# SensorSheet.net
KiCad netlist of a schematic drawn in Altium Designer
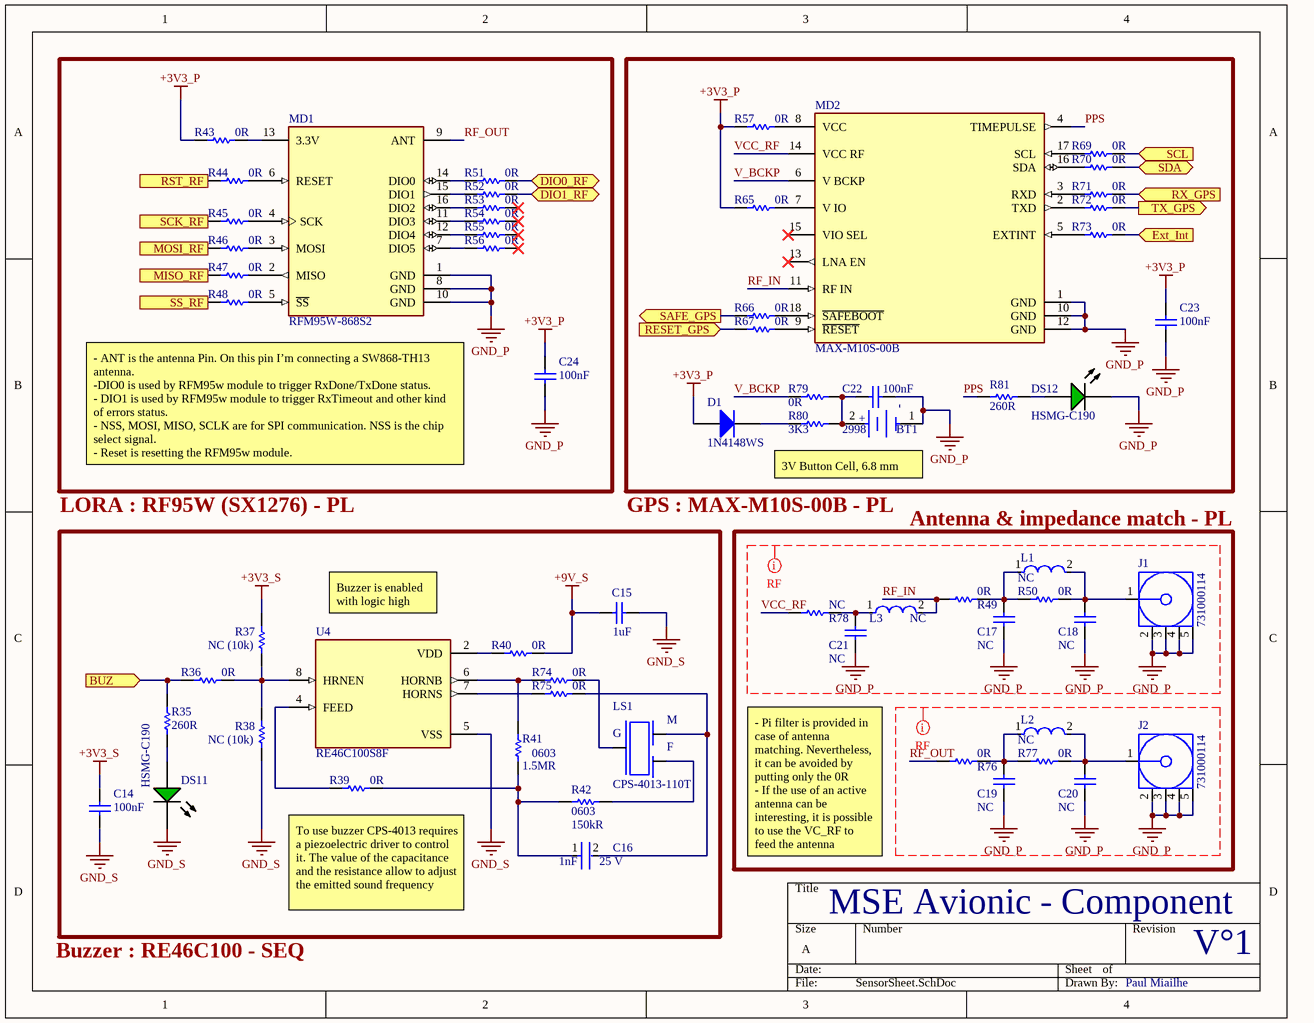
[diagram p0: SensorSheet.SchDoc]

(export (version "E")
  (design (tool "Eeschema 10.0.6"))
  (components
    (comp (ref "BT1")
      (value "2998")
      (footprint "FP-2998-MFG")
      (description "BATTERY RETAINER COIN 6.8MM SMD")
      (libsource (lib "Altium Content Vault") (part "60d3b5b901a8747834971d0eb8cf3fd"))
    )
    (comp (ref "C14")
      (value "GRM21BR71H104KA01L")
      (footprint "CAPC2013X135X45ML10T25")
      (description "Chip Capacitor, 0.1 uF, +/- 10%, 50 V, -55 to 125 degC, 0805 (2012 Metric), RoHS, Tape and Reel")
      (fields
        (field (name "VOLTAGE") "50V")
        (field (name "CAPACITANCE") "100nF")
        (field (name "TOLERANCE") "10%")
      )
      (libsource (lib "Altium Content Vault") (part "CAP-NP-2"))
    )
    (comp (ref "C15")
      (value "GRM188R61E105KA12D")
      (footprint "CAPC1608X90X35LL10T15")
      (fields
        (field (name "MANUFACTURER") "Murata")
        (field (name "CAPACITANCE") "1uF")
        (field (name "TOLERANCE") "10%")
        (field (name "VOLTAGE") "25V")
      )
      (libsource (lib "Altium Content Vault") (part "CAP"))
    )
    (comp (ref "C16")
      (value "C0603C102J3GACTU")
      (footprint "FP-C0603C-CF-MFG")
      (description "CAP CER 1000PF 25V 5% NP0 0603")
      (fields
        (field (name "OCTOPART") "https://octopart.com/c0603c102j3gactu-kemet-8375722")
        (field (name "CAPACITANCE") "1nF")
        (field (name "TOLERANCE") "0.05")
        (field (name "VOLTAGE RATING") "25 V")
      )
      (libsource (lib "Altium Content Vault") (part "b4654b650e69147ec39a6b967a45e02"))
    )
    (comp (ref "C17")
      (value "GRM21BR71H104KA01L")
      (footprint "CAPC2013X135X45ML10T25")
      (description "Chip Capacitor, 0.1 uF, +/- 10%, 50 V, -55 to 125 degC, 0805 (2012 Metric), RoHS, Tape and Reel")
      (fields
        (field (name "VOLTAGE") "50V")
        (field (name "CAPACITANCE") "NC")
        (field (name "TOLERANCE") "10%")
      )
      (libsource (lib "Altium Content Vault") (part "CAP-NP-2"))
    )
    (comp (ref "C18")
      (value "GRM21BR71H104KA01L")
      (footprint "CAPC2013X135X45ML10T25")
      (description "Chip Capacitor, 0.1 uF, +/- 10%, 50 V, -55 to 125 degC, 0805 (2012 Metric), RoHS, Tape and Reel")
      (fields
        (field (name "VOLTAGE") "50V")
        (field (name "CAPACITANCE") "NC")
        (field (name "TOLERANCE") "10%")
      )
      (libsource (lib "Altium Content Vault") (part "CAP-NP-2"))
    )
    (comp (ref "C19")
      (value "GRM21BR71H104KA01L")
      (footprint "CAPC2013X135X45ML10T25")
      (description "Chip Capacitor, 0.1 uF, +/- 10%, 50 V, -55 to 125 degC, 0805 (2012 Metric), RoHS, Tape and Reel")
      (fields
        (field (name "VOLTAGE") "50V")
        (field (name "CAPACITANCE") "NC")
        (field (name "TOLERANCE") "10%")
      )
      (libsource (lib "Altium Content Vault") (part "CAP-NP-2"))
    )
    (comp (ref "C20")
      (value "GRM21BR71H104KA01L")
      (footprint "CAPC2013X135X45ML10T25")
      (description "Chip Capacitor, 0.1 uF, +/- 10%, 50 V, -55 to 125 degC, 0805 (2012 Metric), RoHS, Tape and Reel")
      (fields
        (field (name "VOLTAGE") "50V")
        (field (name "CAPACITANCE") "NC")
        (field (name "TOLERANCE") "10%")
      )
      (libsource (lib "Altium Content Vault") (part "CAP-NP-2"))
    )
    (comp (ref "C21")
      (value "GRM21BR71H104KA01L")
      (footprint "CAPC2013X135X45ML10T25")
      (description "Chip Capacitor, 0.1 uF, +/- 10%, 50 V, -55 to 125 degC, 0805 (2012 Metric), RoHS, Tape and Reel")
      (fields
        (field (name "VOLTAGE") "50V")
        (field (name "CAPACITANCE") "NC")
        (field (name "TOLERANCE") "10%")
      )
      (libsource (lib "Altium Content Vault") (part "CAP-NP-2"))
    )
    (comp (ref "C22")
      (value "GRM21BR71H104KA01L")
      (footprint "CAPC2013X135X45ML10T25")
      (description "Chip Capacitor, 0.1 uF, +/- 10%, 50 V, -55 to 125 degC, 0805 (2012 Metric), RoHS, Tape and Reel")
      (fields
        (field (name "VOLTAGE") "50V")
        (field (name "CAPACITANCE") "100nF")
        (field (name "TOLERANCE") "10%")
      )
      (libsource (lib "Altium Content Vault") (part "CAP-NP-2"))
    )
    (comp (ref "C23")
      (value "GRM21BR71H104KA01L")
      (footprint "CAPC2013X135X45ML10T25")
      (description "Chip Capacitor, 0.1 uF, +/- 10%, 50 V, -55 to 125 degC, 0805 (2012 Metric), RoHS, Tape and Reel")
      (fields
        (field (name "VOLTAGE") "50V")
        (field (name "CAPACITANCE") "100nF")
        (field (name "TOLERANCE") "10%")
      )
      (libsource (lib "Altium Content Vault") (part "CAP-NP-2"))
    )
    (comp (ref "C24")
      (value "GRM21BR71H104KA01L")
      (footprint "CAPC2013X135X45ML10T25")
      (description "Chip Capacitor, 0.1 uF, +/- 10%, 50 V, -55 to 125 degC, 0805 (2012 Metric), RoHS, Tape and Reel")
      (fields
        (field (name "VOLTAGE") "50V")
        (field (name "CAPACITANCE") "100nF")
        (field (name "TOLERANCE") "10%")
      )
      (libsource (lib "Altium Content Vault") (part "CAP-NP-2"))
    )
    (comp (ref "D1")
      (value "1N4148WS")
      (footprint "FAIR-SOD-323_V")
      (description "Small Signal Diode, 75 V, 0.15 A, -55 to 150 degC, 2-Pin SOD-323, RoHS, Tape and Reel")
      (fields (field (name "MANUFACTURER") "Fairchild"))
      (libsource (lib "Saint-Étienne School of Mines- Mines Space") (part "D-AK-2"))
    )
    (comp (ref "DS11")
      (value "HSMG-C190")
      (footprint "AVAG-HSMX-C190_V")
      (description "Chip LED, Green, 2.2 V, -40 to 85 degC, 2-Pin SMD, RoHS, Tape and Reel")
      (libsource (lib "Altium Content Vault") (part "LED-GREEN-AK-2"))
    )
    (comp (ref "DS12")
      (value "HSMG-C190")
      (footprint "AVAG-HSMX-C190_V")
      (description "Chip LED, Green, 2.2 V, -40 to 85 degC, 2-Pin SMD, RoHS, Tape and Reel")
      (libsource (lib "Altium Content Vault") (part "LED-GREEN-AK-2"))
    )
    (comp (ref "J1")
      (value "731000114")
      (footprint "MOLX-731000114_V")
      (description "SMA Right-Angle PCB Jack Receptacle, Brass Body, Gold Plated, 50 Ohm, 5-Pin THD, RoHS, Tray")
      (fields (field (name "MANUFACTURER") "Molex"))
      (libsource (lib "Altium Content Vault") (part "CN-S-4F-RF5"))
    )
    (comp (ref "J2")
      (value "731000114")
      (footprint "MOLX-731000114_V")
      (description "SMA Right-Angle PCB Jack Receptacle, Brass Body, Gold Plated, 50 Ohm, 5-Pin THD, RoHS, Tray")
      (fields (field (name "MANUFACTURER") "Molex"))
      (libsource (lib "Altium Content Vault") (part "CN-S-4F-RF5"))
    )
    (comp (ref "L1")
      (value "NC")
      (footprint "FP-B82422A-MFG")
      (description "FIXED IND 10UH 180MA 1.6 OHM SMD")
      (fields (field (name "TOLERANCE") "10%"))
      (libsource (lib "Altium Content Vault") (part "725321dda6339637d4d059423bc1c3c"))
    )
    (comp (ref "L2")
      (value "NC")
      (footprint "FP-B82422A-MFG")
      (description "FIXED IND 10UH 180MA 1.6 OHM SMD")
      (fields (field (name "TOLERANCE") "10%"))
      (libsource (lib "Altium Content Vault") (part "725321dda6339637d4d059423bc1c3c"))
    )
    (comp (ref "L3")
      (value "NC")
      (footprint "FP-B82422A-MFG")
      (description "FIXED IND 10UH 180MA 1.6 OHM SMD")
      (fields (field (name "TOLERANCE") "10%"))
      (libsource (lib "Altium Content Vault") (part "725321dda6339637d4d059423bc1c3c"))
    )
    (comp (ref "LS1")
      (value "CPS-4013-110T")
      (footprint "XDCR_CPS-4013-110T")
      (description "40 mm, 9 Vdc, 110 dB, Through Hole, Piezo Audio Transducer Buzzer")
      (fields (field (name "MF") "CUI Devices"))
      (libsource (lib "Saint-Étienne School of Mines- Mines Space") (part "CPS-4013-110T"))
    )
    (comp (ref "MD1")
      (value "RFM95W-868S2")
      (footprint "FP-RFM95W-868S2-MFG")
      (description "RX TXRX MODULE ISM < 1GHZ SMD")
      (libsource (lib "Altium Content Vault") (part "17626aa6fba47fab2b206b7c140802e"))
    )
    (comp (ref "MD2")
      (value "MAX-M10S-00B")
      (footprint "FP-MAX-M10S-00B-MFG")
      (description "GNSS LCC RX, ROM, TCXO, LNA, SAW")
      (libsource (lib "Altium Content Vault") (part "a308a25f00fc71354910191737d199d"))
    )
    (comp (ref "R35")
      (value "260R")
      (footprint "RESC1609X50X30NL8T20")
      (fields (field (name "MANUFACTURER") "Vishay Semiconductor"))
      (libsource (lib "Altium Content Vault") (part "RES-2"))
    )
    (comp (ref "R36")
      (value "0R")
      (footprint "RESC1608X55X25ML10T15")
      (description "Chip Resistor, 0 Ohm, +/- 5%, 0.1 W, -55 to 155 degC, 0603 (1608 Metric), RoHS, Tape and Reel")
      (fields (field (name "TOLERANCE") "5%") (field (name "MANUFACTURER") "Yageo"))
      (libsource (lib "Altium Content Vault") (part "RES-2"))
    )
    (comp (ref "R37")
      (value "ERJ3EKF1002V")
      (footprint "RESC1609X55X30LL15T15")
      (description "Chip Resistor, 10 KOhm, +/- 1%, 0.1 W, -55 to 155 degC, 0603 (1608 Metric), RoHS, Tape and Reel")
      (fields
        (field (name "RESISTANCE") "NC (10k)")
        (field (name "TOLERANCE") "1%")
        (field (name "MANUFACTURER") "Panasonic")
      )
      (libsource (lib "Altium Content Vault") (part "RES-2"))
    )
    (comp (ref "R38")
      (value "ERJ3EKF1002V")
      (footprint "RESC1609X55X30LL15T15")
      (description "Chip Resistor, 10 KOhm, +/- 1%, 0.1 W, -55 to 155 degC, 0603 (1608 Metric), RoHS, Tape and Reel")
      (fields
        (field (name "RESISTANCE") "NC (10k)")
        (field (name "TOLERANCE") "1%")
        (field (name "MANUFACTURER") "Panasonic")
      )
      (libsource (lib "Altium Content Vault") (part "RES-2"))
    )
    (comp (ref "R39")
      (value "RC0603JR-070RL")
      (footprint "RESC1608X55X25ML10T15")
      (description "Chip Resistor, 0 Ohm, +/- 5%, 0.1 W, -55 to 155 degC, 0603 (1608 Metric), RoHS, Tape and Reel")
      (fields
        (field (name "TOLERANCE") "5%")
        (field (name "RESISTANCE") "0R")
        (field (name "MANUFACTURER") "Yageo")
      )
      (libsource (lib "Altium Content Vault") (part "RES-2"))
    )
    (comp (ref "R40")
      (value "0R")
      (footprint "RESC1608X55X25ML10T15")
      (description "Chip Resistor, 0 Ohm, +/- 5%, 0.1 W, -55 to 155 degC, 0603 (1608 Metric), RoHS, Tape and Reel")
      (fields (field (name "TOLERANCE") "5%") (field (name "MANUFACTURER") "Yageo"))
      (libsource (lib "Altium Content Vault") (part "RES-2"))
    )
    (comp (ref "R41")
      (value "ERJ-3GEYJ155V")
      (footprint "RESC1608X55X30ML15T15")
      (fields
        (field (name "MANUFACTURER") "Panasonic")
        (field (name "CASE CODE (IMPERIAL)") "0603")
        (field (name "RESISTANCE") "1.5MR")
        (field (name "TOLERANCE") "5%")
      )
      (libsource (lib "Altium Content Vault") (part "RES"))
    )
    (comp (ref "R42")
      (value "ERJ-3EKF1503V")
      (footprint "RESC1608X55X30NL15T15")
      (fields
        (field (name "MANUFACTURER") "Panasonic")
        (field (name "CASE CODE (IMPERIAL)") "0603")
        (field (name "RESISTANCE") "150kR")
        (field (name "TOLERANCE") "1%")
      )
      (libsource (lib "Altium Content Vault") (part "RES"))
    )
    (comp (ref "R43")
      (value "0R")
      (footprint "RESC1608X55X25ML10T15")
      (description "Chip Resistor, 0 Ohm, +/- 5%, 0.1 W, -55 to 155 degC, 0603 (1608 Metric), RoHS, Tape and Reel")
      (fields (field (name "TOLERANCE") "5%") (field (name "MANUFACTURER") "Yageo"))
      (libsource (lib "Altium Content Vault") (part "RES-2"))
    )
    (comp (ref "R44")
      (value "0R")
      (footprint "RESC1608X55X25ML10T15")
      (description "Chip Resistor, 0 Ohm, +/- 5%, 0.1 W, -55 to 155 degC, 0603 (1608 Metric), RoHS, Tape and Reel")
      (fields (field (name "TOLERANCE") "5%") (field (name "MANUFACTURER") "Yageo"))
      (libsource (lib "Altium Content Vault") (part "RES-2"))
    )
    (comp (ref "R45")
      (value "0R")
      (footprint "RESC1608X55X25ML10T15")
      (description "Chip Resistor, 0 Ohm, +/- 5%, 0.1 W, -55 to 155 degC, 0603 (1608 Metric), RoHS, Tape and Reel")
      (fields (field (name "TOLERANCE") "5%") (field (name "MANUFACTURER") "Yageo"))
      (libsource (lib "Altium Content Vault") (part "RES-2"))
    )
    (comp (ref "R46")
      (value "0R")
      (footprint "RESC1608X55X25ML10T15")
      (description "Chip Resistor, 0 Ohm, +/- 5%, 0.1 W, -55 to 155 degC, 0603 (1608 Metric), RoHS, Tape and Reel")
      (fields (field (name "TOLERANCE") "5%") (field (name "MANUFACTURER") "Yageo"))
      (libsource (lib "Altium Content Vault") (part "RES-2"))
    )
    (comp (ref "R47")
      (value "0R")
      (footprint "RESC1608X55X25ML10T15")
      (description "Chip Resistor, 0 Ohm, +/- 5%, 0.1 W, -55 to 155 degC, 0603 (1608 Metric), RoHS, Tape and Reel")
      (fields (field (name "TOLERANCE") "5%") (field (name "MANUFACTURER") "Yageo"))
      (libsource (lib "Altium Content Vault") (part "RES-2"))
    )
    (comp (ref "R48")
      (value "0R")
      (footprint "RESC1608X55X25ML10T15")
      (description "Chip Resistor, 0 Ohm, +/- 5%, 0.1 W, -55 to 155 degC, 0603 (1608 Metric), RoHS, Tape and Reel")
      (fields (field (name "TOLERANCE") "5%") (field (name "MANUFACTURER") "Yageo"))
      (libsource (lib "Altium Content Vault") (part "RES-2"))
    )
    (comp (ref "R49")
      (value "0R")
      (footprint "RESC1608X55X25ML10T15")
      (description "Chip Resistor, 0 Ohm, +/- 5%, 0.1 W, -55 to 155 degC, 0603 (1608 Metric), RoHS, Tape and Reel")
      (fields (field (name "TOLERANCE") "5%") (field (name "MANUFACTURER") "Yageo"))
      (libsource (lib "Altium Content Vault") (part "RES-2"))
    )
    (comp (ref "R50")
      (value "0R")
      (footprint "RESC1608X55X25ML10T15")
      (description "Chip Resistor, 0 Ohm, +/- 5%, 0.1 W, -55 to 155 degC, 0603 (1608 Metric), RoHS, Tape and Reel")
      (fields (field (name "TOLERANCE") "5%") (field (name "MANUFACTURER") "Yageo"))
      (libsource (lib "Altium Content Vault") (part "RES-2"))
    )
    (comp (ref "R51")
      (value "0R")
      (footprint "RESC1608X55X25ML10T15")
      (description "Chip Resistor, 0 Ohm, +/- 5%, 0.1 W, -55 to 155 degC, 0603 (1608 Metric), RoHS, Tape and Reel")
      (fields (field (name "TOLERANCE") "5%") (field (name "MANUFACTURER") "Yageo"))
      (libsource (lib "Altium Content Vault") (part "RES-2"))
    )
    (comp (ref "R52")
      (value "0R")
      (footprint "RESC1608X55X25ML10T15")
      (description "Chip Resistor, 0 Ohm, +/- 5%, 0.1 W, -55 to 155 degC, 0603 (1608 Metric), RoHS, Tape and Reel")
      (fields (field (name "TOLERANCE") "5%") (field (name "MANUFACTURER") "Yageo"))
      (libsource (lib "Altium Content Vault") (part "RES-2"))
    )
    (comp (ref "R53")
      (value "0R")
      (footprint "RESC1608X55X25ML10T15")
      (description "Chip Resistor, 0 Ohm, +/- 5%, 0.1 W, -55 to 155 degC, 0603 (1608 Metric), RoHS, Tape and Reel")
      (fields (field (name "TOLERANCE") "5%") (field (name "MANUFACTURER") "Yageo"))
      (libsource (lib "Altium Content Vault") (part "RES-2"))
    )
    (comp (ref "R54")
      (value "0R")
      (footprint "RESC1608X55X25ML10T15")
      (description "Chip Resistor, 0 Ohm, +/- 5%, 0.1 W, -55 to 155 degC, 0603 (1608 Metric), RoHS, Tape and Reel")
      (fields (field (name "TOLERANCE") "5%") (field (name "MANUFACTURER") "Yageo"))
      (libsource (lib "Altium Content Vault") (part "RES-2"))
    )
    (comp (ref "R55")
      (value "0R")
      (footprint "RESC1608X55X25ML10T15")
      (description "Chip Resistor, 0 Ohm, +/- 5%, 0.1 W, -55 to 155 degC, 0603 (1608 Metric), RoHS, Tape and Reel")
      (fields (field (name "TOLERANCE") "5%") (field (name "MANUFACTURER") "Yageo"))
      (libsource (lib "Altium Content Vault") (part "RES-2"))
    )
    (comp (ref "R56")
      (value "0R")
      (footprint "RESC1608X55X25ML10T15")
      (description "Chip Resistor, 0 Ohm, +/- 5%, 0.1 W, -55 to 155 degC, 0603 (1608 Metric), RoHS, Tape and Reel")
      (fields (field (name "TOLERANCE") "5%") (field (name "MANUFACTURER") "Yageo"))
      (libsource (lib "Altium Content Vault") (part "RES-2"))
    )
    (comp (ref "R57")
      (value "0R")
      (footprint "RESC1608X55X25ML10T15")
      (description "Chip Resistor, 0 Ohm, +/- 5%, 0.1 W, -55 to 155 degC, 0603 (1608 Metric), RoHS, Tape and Reel")
      (fields (field (name "TOLERANCE") "5%") (field (name "MANUFACTURER") "Yageo"))
      (libsource (lib "Altium Content Vault") (part "RES-2"))
    )
    (comp (ref "R65")
      (value "0R")
      (footprint "RESC1608X55X25ML10T15")
      (description "Chip Resistor, 0 Ohm, +/- 5%, 0.1 W, -55 to 155 degC, 0603 (1608 Metric), RoHS, Tape and Reel")
      (fields (field (name "TOLERANCE") "5%") (field (name "MANUFACTURER") "Yageo"))
      (libsource (lib "Altium Content Vault") (part "RES-2"))
    )
    (comp (ref "R66")
      (value "0R")
      (footprint "RESC1608X55X25ML10T15")
      (description "Chip Resistor, 0 Ohm, +/- 5%, 0.1 W, -55 to 155 degC, 0603 (1608 Metric), RoHS, Tape and Reel")
      (fields (field (name "TOLERANCE") "5%") (field (name "MANUFACTURER") "Yageo"))
      (libsource (lib "Altium Content Vault") (part "RES-2"))
    )
    (comp (ref "R67")
      (value "0R")
      (footprint "RESC1608X55X25ML10T15")
      (description "Chip Resistor, 0 Ohm, +/- 5%, 0.1 W, -55 to 155 degC, 0603 (1608 Metric), RoHS, Tape and Reel")
      (fields (field (name "TOLERANCE") "5%") (field (name "MANUFACTURER") "Yageo"))
      (libsource (lib "Altium Content Vault") (part "RES-2"))
    )
    (comp (ref "R69")
      (value "0R")
      (footprint "RESC1608X55X25ML10T15")
      (description "Chip Resistor, 0 Ohm, +/- 5%, 0.1 W, -55 to 155 degC, 0603 (1608 Metric), RoHS, Tape and Reel")
      (fields (field (name "TOLERANCE") "5%") (field (name "MANUFACTURER") "Yageo"))
      (libsource (lib "Altium Content Vault") (part "RES-2"))
    )
    (comp (ref "R70")
      (value "0R")
      (footprint "RESC1608X55X25ML10T15")
      (description "Chip Resistor, 0 Ohm, +/- 5%, 0.1 W, -55 to 155 degC, 0603 (1608 Metric), RoHS, Tape and Reel")
      (fields (field (name "TOLERANCE") "5%") (field (name "MANUFACTURER") "Yageo"))
      (libsource (lib "Altium Content Vault") (part "RES-2"))
    )
    (comp (ref "R71")
      (value "0R")
      (footprint "RESC1608X55X25ML10T15")
      (description "Chip Resistor, 0 Ohm, +/- 5%, 0.1 W, -55 to 155 degC, 0603 (1608 Metric), RoHS, Tape and Reel")
      (fields (field (name "TOLERANCE") "5%") (field (name "MANUFACTURER") "Yageo"))
      (libsource (lib "Altium Content Vault") (part "RES-2"))
    )
    (comp (ref "R72")
      (value "0R")
      (footprint "RESC1608X55X25ML10T15")
      (description "Chip Resistor, 0 Ohm, +/- 5%, 0.1 W, -55 to 155 degC, 0603 (1608 Metric), RoHS, Tape and Reel")
      (fields (field (name "TOLERANCE") "5%") (field (name "MANUFACTURER") "Yageo"))
      (libsource (lib "Altium Content Vault") (part "RES-2"))
    )
    (comp (ref "R73")
      (value "0R")
      (footprint "RESC1608X55X25ML10T15")
      (description "Chip Resistor, 0 Ohm, +/- 5%, 0.1 W, -55 to 155 degC, 0603 (1608 Metric), RoHS, Tape and Reel")
      (fields (field (name "TOLERANCE") "5%") (field (name "MANUFACTURER") "Yageo"))
      (libsource (lib "Altium Content Vault") (part "RES-2"))
    )
    (comp (ref "R74")
      (value "0R")
      (footprint "RESC1608X55X25ML10T15")
      (description "Chip Resistor, 0 Ohm, +/- 5%, 0.1 W, -55 to 155 degC, 0603 (1608 Metric), RoHS, Tape and Reel")
      (fields (field (name "TOLERANCE") "5%") (field (name "MANUFACTURER") "Yageo"))
      (libsource (lib "Altium Content Vault") (part "RES-2"))
    )
    (comp (ref "R75")
      (value "0R")
      (footprint "RESC1608X55X25ML10T15")
      (description "Chip Resistor, 0 Ohm, +/- 5%, 0.1 W, -55 to 155 degC, 0603 (1608 Metric), RoHS, Tape and Reel")
      (fields (field (name "TOLERANCE") "5%") (field (name "MANUFACTURER") "Yageo"))
      (libsource (lib "Altium Content Vault") (part "RES-2"))
    )
    (comp (ref "R76")
      (value "0R")
      (footprint "RESC1608X55X25ML10T15")
      (description "Chip Resistor, 0 Ohm, +/- 5%, 0.1 W, -55 to 155 degC, 0603 (1608 Metric), RoHS, Tape and Reel")
      (fields (field (name "TOLERANCE") "5%") (field (name "MANUFACTURER") "Yageo"))
      (libsource (lib "Altium Content Vault") (part "RES-2"))
    )
    (comp (ref "R77")
      (value "0R")
      (footprint "RESC1608X55X25ML10T15")
      (description "Chip Resistor, 0 Ohm, +/- 5%, 0.1 W, -55 to 155 degC, 0603 (1608 Metric), RoHS, Tape and Reel")
      (fields (field (name "TOLERANCE") "5%") (field (name "MANUFACTURER") "Yageo"))
      (libsource (lib "Altium Content Vault") (part "RES-2"))
    )
    (comp (ref "R78")
      (value "NC")
      (footprint "RESC1608X55X25ML10T15")
      (description "Chip Resistor, 0 Ohm, +/- 5%, 0.1 W, -55 to 155 degC, 0603 (1608 Metric), RoHS, Tape and Reel")
      (fields (field (name "TOLERANCE") "5%") (field (name "MANUFACTURER") "Yageo"))
      (libsource (lib "Altium Content Vault") (part "RES-2"))
    )
    (comp (ref "R79")
      (value "0R")
      (footprint "RESC1608X55X25ML10T15")
      (description "Chip Resistor, 0 Ohm, +/- 5%, 0.1 W, -55 to 155 degC, 0603 (1608 Metric), RoHS, Tape and Reel")
      (fields (field (name "TOLERANCE") "5%") (field (name "MANUFACTURER") "Yageo"))
      (libsource (lib "Altium Content Vault") (part "RES-2"))
    )
    (comp (ref "R80")
      (value "RC0603FR-073K3L")
      (footprint "RESC1608X55X25ML10T15")
      (description "Chip Resistor, 3.3 KOhm, +/- 1%, 0.1 W, -55 to 155 degC, 0603 (1608 Metric), RoHS, Tape and Reel")
      (fields
        (field (name "RESISTANCE") "3K3")
        (field (name "MANUFACTURER") "Yageo")
        (field (name "TOLERANCE") "1%")
      )
      (libsource (lib "Altium Content Vault") (part "RES-2"))
    )
    (comp (ref "R81")
      (value "260R")
      (footprint "RESC1609X50X30NL8T20")
      (fields (field (name "MANUFACTURER") "Vishay Semiconductor"))
      (libsource (lib "Altium Content Vault") (part "RES-2"))
    )
    (comp (ref "U4")
      (value "RE46C100S8F")
      (footprint "SOIC127P600X175-8N")
      (description "IC HORN DRIVER DUAL 8SOIC")
      (fields
        (field (name "DIGI-KEY_PART_NUMBER") "RE46C100S8F-ND")
        (field (name "MF") "Microchip Technology")
      )
      (libsource (lib "Saint-Étienne School of Mines- Mines Space") (part "RE46C100S8F"))
    )
  )
  (nets
    (net (code "1") (name "+3V3_P") (class "Default")
      (node (ref "C23") (pin "2") (pinfunction "2_2") (pintype "passive"))
      (node (ref "C24") (pin "2") (pinfunction "2_2") (pintype "passive"))
      (node (ref "D1") (pin "1") (pinfunction "A_1") (pintype "passive"))
      (node (ref "R43") (pin "1") (pinfunction "1_1") (pintype "passive"))
      (node (ref "R57") (pin "1") (pinfunction "1_1") (pintype "passive"))
      (node (ref "R65") (pin "1") (pinfunction "1_1") (pintype "passive"))
    )
    (net (code "2") (name "+3V3_S") (class "Default")
      (node (ref "C14") (pin "2") (pinfunction "2_2") (pintype "passive"))
      (node (ref "R37") (pin "2") (pinfunction "2_2") (pintype "passive"))
    )
    (net (code "3") (name "+9V_S") (class "Default")
      (node (ref "C15") (pin "1") (pinfunction "1_1") (pintype "passive"))
      (node (ref "R40") (pin "2") (pinfunction "2_2") (pintype "passive"))
    )
    (net (code "4") (name "/BUZ") (class "Default")
      (node (ref "R35") (pin "1") (pinfunction "1_1") (pintype "passive"))
      (node (ref "R36") (pin "1") (pinfunction "1_1") (pintype "passive"))
    )
    (net (code "5") (name "/DIO0_RF") (class "Default")
      (node (ref "R51") (pin "2") (pinfunction "2_2") (pintype "passive"))
    )
    (net (code "6") (name "/DIO1_RF") (class "Default")
      (node (ref "R52") (pin "2") (pinfunction "2_2") (pintype "passive"))
    )
    (net (code "7") (name "/Ext_Int") (class "Default")
      (node (ref "R73") (pin "2") (pinfunction "2_2") (pintype "passive"))
    )
    (net (code "8") (name "/MISO_RF") (class "Default")
      (node (ref "R47") (pin "1") (pinfunction "1_1") (pintype "passive"))
    )
    (net (code "9") (name "/MOSI_RF") (class "Default")
      (node (ref "R46") (pin "1") (pinfunction "1_1") (pintype "passive"))
    )
    (net (code "10") (name "/PPS") (class "Default")
      (node (ref "MD2") (pin "4") (pinfunction "TIMEPULSE_4") (pintype "output"))
      (node (ref "R81") (pin "1") (pinfunction "1_1") (pintype "passive"))
    )
    (net (code "11") (name "/RESET_GPS") (class "Default")
      (node (ref "R67") (pin "1") (pinfunction "1_1") (pintype "passive"))
    )
    (net (code "12") (name "/RF_IN") (class "Default")
      (node (ref "L3") (pin "2") (pinfunction "2_2") (pintype "passive"))
      (node (ref "MD2") (pin "11") (pinfunction "RF_IN_11") (pintype "input"))
      (node (ref "R49") (pin "1") (pinfunction "1_1") (pintype "passive"))
    )
    (net (code "13") (name "/RF_OUT") (class "Default")
      (node (ref "MD1") (pin "9") (pinfunction "ANT_9") (pintype "passive"))
      (node (ref "R76") (pin "1") (pinfunction "1_1") (pintype "passive"))
    )
    (net (code "14") (name "/RST_RF") (class "Default")
      (node (ref "R44") (pin "1") (pinfunction "1_1") (pintype "passive"))
    )
    (net (code "15") (name "/RX_GPS") (class "Default")
      (node (ref "R71") (pin "2") (pinfunction "2_2") (pintype "passive"))
    )
    (net (code "16") (name "/SAFE_GPS") (class "Default")
      (node (ref "R66") (pin "1") (pinfunction "1_1") (pintype "passive"))
    )
    (net (code "17") (name "/SCK_RF") (class "Default")
      (node (ref "R45") (pin "1") (pinfunction "1_1") (pintype "passive"))
    )
    (net (code "18") (name "/SCL") (class "Default")
      (node (ref "R69") (pin "2") (pinfunction "2_2") (pintype "passive"))
    )
    (net (code "19") (name "/SDA") (class "Default")
      (node (ref "R70") (pin "2") (pinfunction "2_2") (pintype "passive"))
    )
    (net (code "20") (name "/SS_RF") (class "Default")
      (node (ref "R48") (pin "1") (pinfunction "1_1") (pintype "passive"))
    )
    (net (code "21") (name "/TX_GPS") (class "Default")
      (node (ref "R72") (pin "2") (pinfunction "2_2") (pintype "passive"))
    )
    (net (code "22") (name "/VCC_RF") (class "Default")
      (node (ref "MD2") (pin "14") (pinfunction "VCC_RF_14") (pintype "power_in"))
      (node (ref "R78") (pin "1") (pinfunction "1_1") (pintype "passive"))
    )
    (net (code "23") (name "/V_BCKP") (class "Default")
      (node (ref "MD2") (pin "6") (pinfunction "V_BCKP_6") (pintype "power_in"))
      (node (ref "R79") (pin "1") (pinfunction "1_1") (pintype "passive"))
    )
    (net (code "24") (name "GND_P") (class "Default")
      (node (ref "BT1") (pin "1") (pinfunction "C_1") (pintype "passive"))
      (node (ref "C17") (pin "1") (pinfunction "1_1") (pintype "passive"))
      (node (ref "C18") (pin "1") (pinfunction "1_1") (pintype "passive"))
      (node (ref "C19") (pin "1") (pinfunction "1_1") (pintype "passive"))
      (node (ref "C20") (pin "1") (pinfunction "1_1") (pintype "passive"))
      (node (ref "C21") (pin "1") (pinfunction "1_1") (pintype "passive"))
      (node (ref "C22") (pin "1") (pinfunction "1_1") (pintype "passive"))
      (node (ref "C23") (pin "1") (pinfunction "1_1") (pintype "passive"))
      (node (ref "C24") (pin "1") (pinfunction "1_1") (pintype "passive"))
      (node (ref "DS12") (pin "2") (pinfunction "K_2") (pintype "passive"))
      (node (ref "J1") (pin "2") (pinfunction "2_2") (pintype "passive"))
      (node (ref "J1") (pin "3") (pinfunction "3_3") (pintype "passive"))
      (node (ref "J1") (pin "4") (pinfunction "4_4") (pintype "passive"))
      (node (ref "J1") (pin "5") (pinfunction "5_5") (pintype "passive"))
      (node (ref "J2") (pin "2") (pinfunction "2_2") (pintype "passive"))
      (node (ref "J2") (pin "3") (pinfunction "3_3") (pintype "passive"))
      (node (ref "J2") (pin "4") (pinfunction "4_4") (pintype "passive"))
      (node (ref "J2") (pin "5") (pinfunction "5_5") (pintype "passive"))
      (node (ref "MD1") (pin "1") (pinfunction "GND_1") (pintype "power_in"))
      (node (ref "MD1") (pin "10") (pinfunction "GND_10") (pintype "power_in"))
      (node (ref "MD1") (pin "8") (pinfunction "GND_8") (pintype "power_in"))
      (node (ref "MD2") (pin "1") (pinfunction "GND_1") (pintype "power_in"))
      (node (ref "MD2") (pin "10") (pinfunction "GND_10") (pintype "power_in"))
      (node (ref "MD2") (pin "12") (pinfunction "GND_12") (pintype "power_in"))
    )
    (net (code "25") (name "GND_S") (class "Default")
      (node (ref "C14") (pin "1") (pinfunction "1_1") (pintype "passive"))
      (node (ref "C15") (pin "2") (pinfunction "2_2") (pintype "passive"))
      (node (ref "DS11") (pin "2") (pinfunction "K_2") (pintype "passive"))
      (node (ref "R38") (pin "1") (pinfunction "1_1") (pintype "passive"))
      (node (ref "U4") (pin "5") (pinfunction "VSS_5") (pintype "power_in"))
    )
    (net (code "26") (name "Net-(BT1-A)") (class "Default")
      (node (ref "BT1") (pin "2") (pinfunction "A_2") (pintype "passive"))
      (node (ref "C22") (pin "2") (pinfunction "2_2") (pintype "passive"))
      (node (ref "R79") (pin "2") (pinfunction "2_2") (pintype "passive"))
      (node (ref "R80") (pin "1") (pinfunction "1_1") (pintype "passive"))
    )
    (net (code "27") (name "Net-(C16-Pad1)") (class "Default")
      (node (ref "C16") (pin "1") (pinfunction "1_1") (pintype "passive"))
      (node (ref "R39") (pin "2") (pinfunction "2_2") (pintype "passive"))
      (node (ref "R41") (pin "1") (pinfunction "1_1") (pintype "passive"))
      (node (ref "R42") (pin "1") (pinfunction "1_1") (pintype "passive"))
    )
    (net (code "28") (name "Net-(C17-Pad2)") (class "Default")
      (node (ref "C17") (pin "2") (pinfunction "2_2") (pintype "passive"))
      (node (ref "L1") (pin "1") (pinfunction "1_1") (pintype "passive"))
      (node (ref "R49") (pin "2") (pinfunction "2_2") (pintype "passive"))
      (node (ref "R50") (pin "1") (pinfunction "1_1") (pintype "passive"))
    )
    (net (code "29") (name "Net-(C18-Pad2)") (class "Default")
      (node (ref "C18") (pin "2") (pinfunction "2_2") (pintype "passive"))
      (node (ref "J1") (pin "1") (pinfunction "1_1") (pintype "passive"))
      (node (ref "L1") (pin "2") (pinfunction "2_2") (pintype "passive"))
      (node (ref "R50") (pin "2") (pinfunction "2_2") (pintype "passive"))
    )
    (net (code "30") (name "Net-(C19-Pad2)") (class "Default")
      (node (ref "C19") (pin "2") (pinfunction "2_2") (pintype "passive"))
      (node (ref "L2") (pin "1") (pinfunction "1_1") (pintype "passive"))
      (node (ref "R76") (pin "2") (pinfunction "2_2") (pintype "passive"))
      (node (ref "R77") (pin "1") (pinfunction "1_1") (pintype "passive"))
    )
    (net (code "31") (name "Net-(C20-Pad2)") (class "Default")
      (node (ref "C20") (pin "2") (pinfunction "2_2") (pintype "passive"))
      (node (ref "J2") (pin "1") (pinfunction "1_1") (pintype "passive"))
      (node (ref "L2") (pin "2") (pinfunction "2_2") (pintype "passive"))
      (node (ref "R77") (pin "2") (pinfunction "2_2") (pintype "passive"))
    )
    (net (code "32") (name "Net-(C21-Pad2)") (class "Default")
      (node (ref "C21") (pin "2") (pinfunction "2_2") (pintype "passive"))
      (node (ref "L3") (pin "1") (pinfunction "1_1") (pintype "passive"))
      (node (ref "R78") (pin "2") (pinfunction "2_2") (pintype "passive"))
    )
    (net (code "33") (name "Net-(D1-K)") (class "Default")
      (node (ref "D1") (pin "2") (pinfunction "K_2") (pintype "passive"))
      (node (ref "R80") (pin "2") (pinfunction "2_2") (pintype "passive"))
    )
    (net (code "34") (name "Net-(DS11-A)") (class "Default")
      (node (ref "DS11") (pin "1") (pinfunction "A_1") (pintype "passive"))
      (node (ref "R35") (pin "2") (pinfunction "2_2") (pintype "passive"))
    )
    (net (code "35") (name "Net-(DS12-A)") (class "Default")
      (node (ref "DS12") (pin "1") (pinfunction "A_1") (pintype "passive"))
      (node (ref "R81") (pin "2") (pinfunction "2_2") (pintype "passive"))
    )
    (net (code "36") (name "Net-(LS1-F)") (class "Default")
      (node (ref "LS1") (pin "2") (pinfunction "F_2") (pintype "passive"))
      (node (ref "R42") (pin "2") (pinfunction "2_2") (pintype "passive"))
    )
    (net (code "37") (name "Net-(LS1-G)") (class "Default")
      (node (ref "LS1") (pin "3") (pinfunction "G_3") (pintype "passive"))
      (node (ref "R74") (pin "1") (pinfunction "1_1") (pintype "passive"))
    )
    (net (code "38") (name "Net-(LS1-M)") (class "Default")
      (node (ref "C16") (pin "2") (pinfunction "2_2") (pintype "passive"))
      (node (ref "LS1") (pin "1") (pinfunction "M_1") (pintype "passive"))
      (node (ref "R75") (pin "2") (pinfunction "2_2") (pintype "passive"))
    )
    (net (code "39") (name "Net-(MD1-3.3V)") (class "Default")
      (node (ref "MD1") (pin "13") (pinfunction "3.3V_13") (pintype "power_in"))
      (node (ref "R43") (pin "2") (pinfunction "2_2") (pintype "passive"))
    )
    (net (code "40") (name "Net-(MD1-DIO0)") (class "Default")
      (node (ref "MD1") (pin "14") (pinfunction "DIO0_14") (pintype "bidirectional"))
      (node (ref "R51") (pin "1") (pinfunction "1_1") (pintype "passive"))
    )
    (net (code "41") (name "Net-(MD1-DIO1)") (class "Default")
      (node (ref "MD1") (pin "15") (pinfunction "DIO1_15") (pintype "output"))
      (node (ref "R52") (pin "1") (pinfunction "1_1") (pintype "passive"))
    )
    (net (code "42") (name "Net-(MD1-DIO2)") (class "Default")
      (node (ref "MD1") (pin "16") (pinfunction "DIO2_16") (pintype "bidirectional"))
      (node (ref "R53") (pin "1") (pinfunction "1_1") (pintype "passive"))
    )
    (net (code "43") (name "Net-(MD1-DIO3)") (class "Default")
      (node (ref "MD1") (pin "11") (pinfunction "DIO3_11") (pintype "bidirectional"))
      (node (ref "R54") (pin "1") (pinfunction "1_1") (pintype "passive"))
    )
    (net (code "44") (name "Net-(MD1-DIO4)") (class "Default")
      (node (ref "MD1") (pin "12") (pinfunction "DIO4_12") (pintype "bidirectional"))
      (node (ref "R55") (pin "1") (pinfunction "1_1") (pintype "passive"))
    )
    (net (code "45") (name "Net-(MD1-DIO5)") (class "Default")
      (node (ref "MD1") (pin "7") (pinfunction "DIO5_7") (pintype "bidirectional"))
      (node (ref "R56") (pin "1") (pinfunction "1_1") (pintype "passive"))
    )
    (net (code "46") (name "Net-(MD1-MISO)") (class "Default")
      (node (ref "MD1") (pin "2") (pinfunction "MISO_2") (pintype "output"))
      (node (ref "R47") (pin "2") (pinfunction "2_2") (pintype "passive"))
    )
    (net (code "47") (name "Net-(MD1-MOSI)") (class "Default")
      (node (ref "MD1") (pin "3") (pinfunction "MOSI_3") (pintype "input"))
      (node (ref "R46") (pin "2") (pinfunction "2_2") (pintype "passive"))
    )
    (net (code "48") (name "Net-(MD1-RESET)") (class "Default")
      (node (ref "MD1") (pin "6") (pinfunction "RESET_6") (pintype "input"))
      (node (ref "R44") (pin "2") (pinfunction "2_2") (pintype "passive"))
    )
    (net (code "49") (name "Net-(MD1-SCK)") (class "Default")
      (node (ref "MD1") (pin "4") (pinfunction "SCK_4") (pintype "input"))
      (node (ref "R45") (pin "2") (pinfunction "2_2") (pintype "passive"))
    )
    (net (code "50") (name "Net-(MD1-~{SS})") (class "Default")
      (node (ref "MD1") (pin "5") (pinfunction "~{SS}_5") (pintype "input"))
      (node (ref "R48") (pin "2") (pinfunction "2_2") (pintype "passive"))
    )
    (net (code "51") (name "Net-(MD2-EXTINT)") (class "Default")
      (node (ref "MD2") (pin "5") (pinfunction "EXTINT_5") (pintype "input"))
      (node (ref "R73") (pin "1") (pinfunction "1_1") (pintype "passive"))
    )
    (net (code "52") (name "Net-(MD2-RXD)") (class "Default")
      (node (ref "MD2") (pin "3") (pinfunction "RXD_3") (pintype "input"))
      (node (ref "R71") (pin "1") (pinfunction "1_1") (pintype "passive"))
    )
    (net (code "53") (name "Net-(MD2-SCL)") (class "Default")
      (node (ref "MD2") (pin "17") (pinfunction "SCL_17") (pintype "input"))
      (node (ref "R69") (pin "1") (pinfunction "1_1") (pintype "passive"))
    )
    (net (code "54") (name "Net-(MD2-SDA)") (class "Default")
      (node (ref "MD2") (pin "16") (pinfunction "SDA_16") (pintype "bidirectional"))
      (node (ref "R70") (pin "1") (pinfunction "1_1") (pintype "passive"))
    )
    (net (code "55") (name "Net-(MD2-TXD)") (class "Default")
      (node (ref "MD2") (pin "2") (pinfunction "TXD_2") (pintype "output"))
      (node (ref "R72") (pin "1") (pinfunction "1_1") (pintype "passive"))
    )
    (net (code "56") (name "Net-(MD2-VCC)") (class "Default")
      (node (ref "MD2") (pin "8") (pinfunction "VCC_8") (pintype "power_in"))
      (node (ref "R57") (pin "2") (pinfunction "2_2") (pintype "passive"))
    )
    (net (code "57") (name "Net-(MD2-V_IO)") (class "Default")
      (node (ref "MD2") (pin "7") (pinfunction "V_IO_7") (pintype "power_in"))
      (node (ref "R65") (pin "2") (pinfunction "2_2") (pintype "passive"))
    )
    (net (code "58") (name "Net-(MD2-~{RESET})") (class "Default")
      (node (ref "MD2") (pin "9") (pinfunction "~{RESET}_9") (pintype "input"))
      (node (ref "R67") (pin "2") (pinfunction "2_2") (pintype "passive"))
    )
    (net (code "59") (name "Net-(MD2-~{SAFEBOOT})") (class "Default")
      (node (ref "MD2") (pin "18") (pinfunction "~{SAFEBOOT}_18") (pintype "input"))
      (node (ref "R66") (pin "2") (pinfunction "2_2") (pintype "passive"))
    )
    (net (code "60") (name "Net-(U4-FEED)") (class "Default")
      (node (ref "R39") (pin "1") (pinfunction "1_1") (pintype "passive"))
      (node (ref "U4") (pin "4") (pinfunction "FEED_4") (pintype "input"))
    )
    (net (code "61") (name "Net-(U4-HORNB)") (class "Default")
      (node (ref "R41") (pin "2") (pinfunction "2_2") (pintype "passive"))
      (node (ref "R74") (pin "2") (pinfunction "2_2") (pintype "passive"))
      (node (ref "U4") (pin "6") (pinfunction "HORNB_6") (pintype "output"))
    )
    (net (code "62") (name "Net-(U4-HORNS)") (class "Default")
      (node (ref "R75") (pin "1") (pinfunction "1_1") (pintype "passive"))
      (node (ref "U4") (pin "7") (pinfunction "HORNS_7") (pintype "output"))
    )
    (net (code "63") (name "Net-(U4-HRNEN)") (class "Default")
      (node (ref "R36") (pin "2") (pinfunction "2_2") (pintype "passive"))
      (node (ref "R37") (pin "1") (pinfunction "1_1") (pintype "passive"))
      (node (ref "R38") (pin "2") (pinfunction "2_2") (pintype "passive"))
      (node (ref "U4") (pin "8") (pinfunction "HRNEN_8") (pintype "input"))
    )
    (net (code "64") (name "Net-(U4-VDD)") (class "Default")
      (node (ref "R40") (pin "1") (pinfunction "1_1") (pintype "passive"))
      (node (ref "U4") (pin "2") (pinfunction "VDD_2") (pintype "power_in"))
    )
    (net (code "65") (name "unconnected-(MD2-LNA_EN-Pad13)") (class "Default")
      (node (ref "MD2") (pin "13") (pinfunction "LNA_EN_13") (pintype "output+no_connect"))
    )
    (net (code "66") (name "unconnected-(MD2-VIO_SEL-Pad15)") (class "Default")
      (node (ref "MD2") (pin "15") (pinfunction "VIO_SEL_15") (pintype "power_in+no_connect"))
    )
    (net (code "67") (name "unconnected-(R53-Pad2)") (class "Default")
      (node (ref "R53") (pin "2") (pinfunction "2_2") (pintype "passive+no_connect"))
    )
    (net (code "68") (name "unconnected-(R54-Pad2)") (class "Default")
      (node (ref "R54") (pin "2") (pinfunction "2_2") (pintype "passive+no_connect"))
    )
    (net (code "69") (name "unconnected-(R55-Pad2)") (class "Default")
      (node (ref "R55") (pin "2") (pinfunction "2_2") (pintype "passive+no_connect"))
    )
    (net (code "70") (name "unconnected-(R56-Pad2)") (class "Default")
      (node (ref "R56") (pin "2") (pinfunction "2_2") (pintype "passive+no_connect"))
    )
  )
)
